# Interlock.net
KiCad netlist of a schematic drawn in Altium Designer
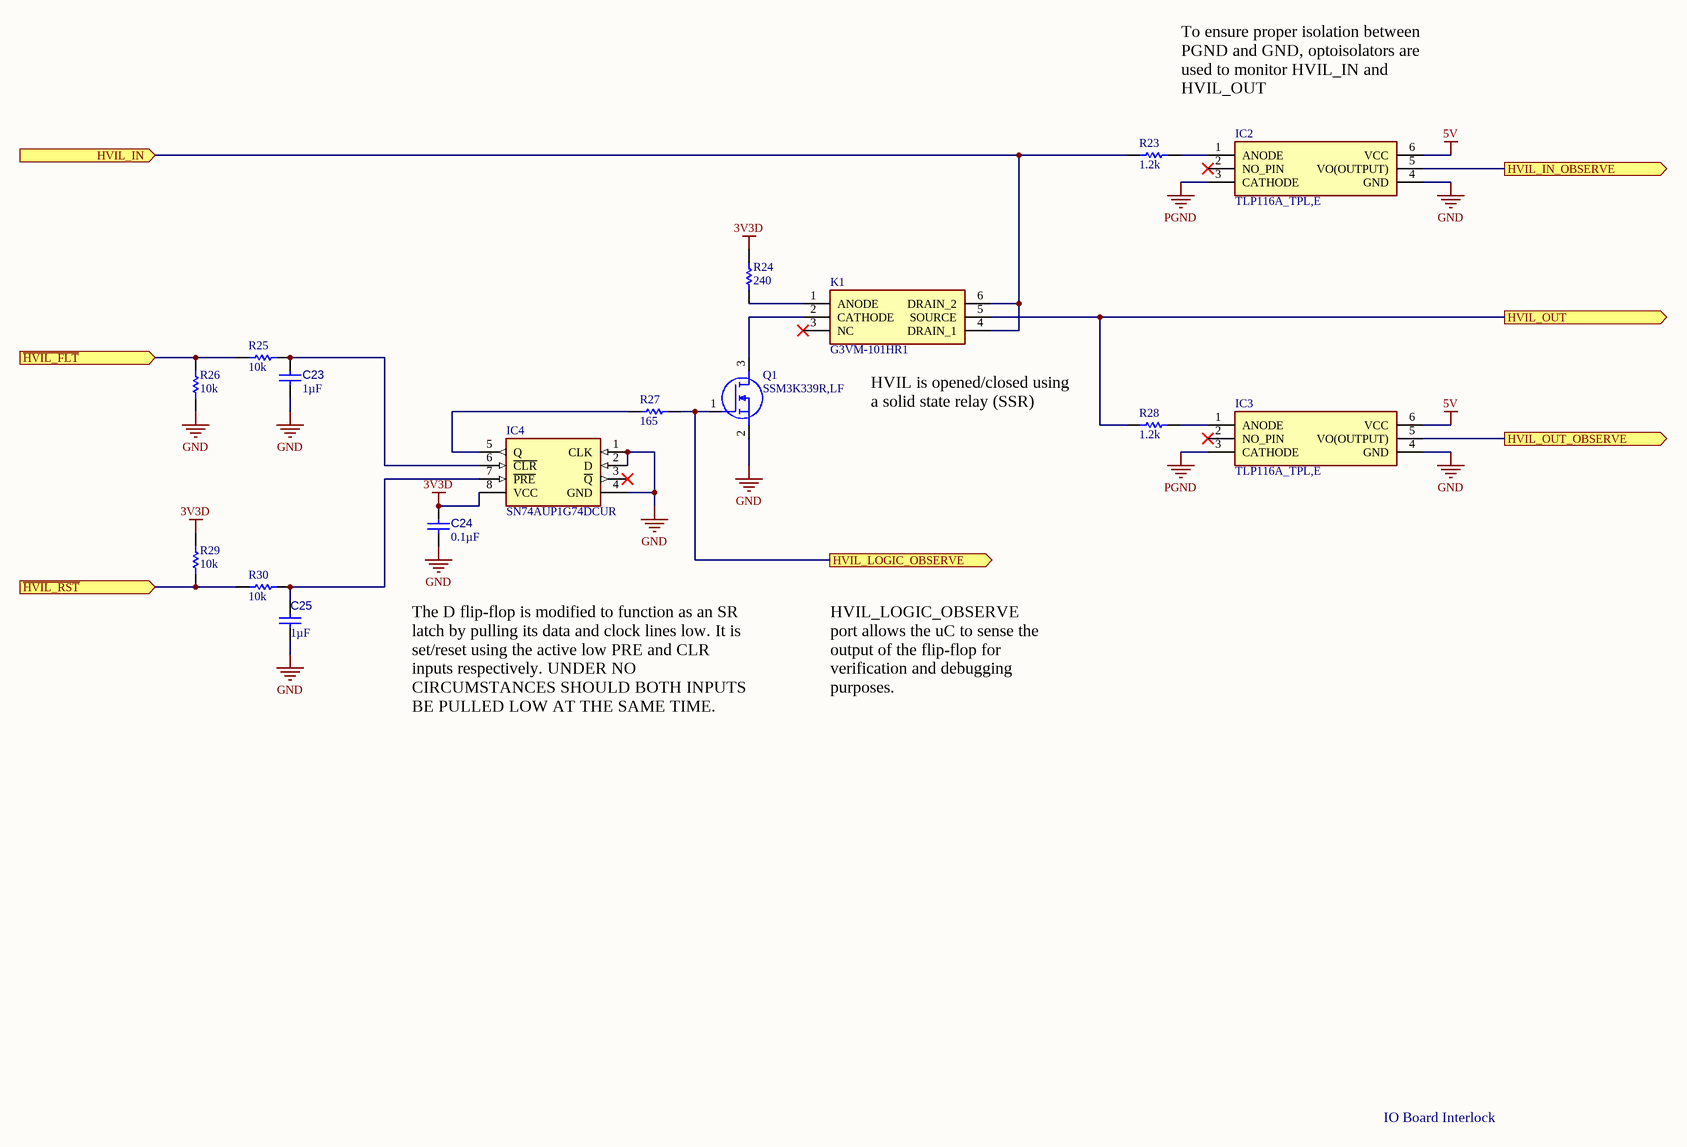
[diagram p0: Interlock.SchDoc]

(export (version "E")
  (design (tool "Eeschema 10.0.6"))
  (components
    (comp (ref "C23")
      (value "1µF")
      (footprint "CAPC2013X145X50ML20T25")
      (description "Chip Capacitor, 1 uF, +/-10%, 25 V, 0805 (2012 Metric)")
      (fields (field (name "TOLERANCE") "10%"))
      (libsource (lib "Caltech FSAE") (part "CAP-NP-2"))
    )
    (comp (ref "C24")
      (value "0.1µF")
      (footprint "CAPC2013X145X50ML20T25")
      (description "Chip Capacitor, 0.1 uF, +/-10%, 25 V, 0805 (2012 Metric)")
      (fields (field (name "TOLERANCE") "10%"))
      (libsource (lib "Caltech FSAE") (part "CAP-NP-2"))
    )
    (comp (ref "C25")
      (value "1µF")
      (footprint "CAPC2013X145X50ML20T25")
      (description "Chip Capacitor, 1 uF, +/-10%, 25 V, 0805 (2012 Metric)")
      (fields (field (name "TOLERANCE") "10%"))
      (libsource (lib "Caltech FSAE") (part "CAP-NP-2"))
    )
    (comp (ref "IC2")
      (value "TLP116A_TPL,E")
      (footprint "SOT127P700X230-6N")
      (description "Integrated Circuit")
      (fields
        (field (name "MANUFACTURER_PART_NUMBER") "TLP116A(TPL,E")
        (field (name "MOUSER PART NUMBER") "757-TLP116A(TPLE")
      )
      (libsource (lib "uControllerTemplate2021") (part "TLP116A_TPL,E"))
    )
    (comp (ref "IC3")
      (value "TLP116A_TPL,E")
      (footprint "SOT127P700X230-6N")
      (description "Integrated Circuit")
      (fields
        (field (name "MANUFACTURER_PART_NUMBER") "TLP116A(TPL,E")
        (field (name "MOUSER PART NUMBER") "757-TLP116A(TPLE")
      )
      (libsource (lib "uControllerTemplate2021") (part "TLP116A_TPL,E"))
    )
    (comp (ref "IC4")
      (value "SN74AUP1G74DCUR")
      (footprint "SOT50P310X90-8N")
      (description "Integrated Circuit")
      (fields (field (name "MOUSER PART NUMBER") "595-SN74AUP1G74DCUR"))
      (libsource (lib "uControllerTemplate2021") (part "SN74AUP1G74DCUR"))
    )
    (comp (ref "K1")
      (value "G3VM-101HR1")
      (footprint "G3VM101HR1")
      (description "Relay or Contactor")
      (fields (field (name "MOUSER PART NUMBER") "653-G3VM-101HR1"))
      (libsource (lib "uControllerTemplate2021") (part "G3VM-101HR1"))
    )
    (comp (ref "Q1")
      (value "SSM3K339R,LF")
      (footprint "SOTFL95P240X88-3N")
      (description "MOSFET (N-Channel)")
      (fields (field (name "MOUSER PART NUMBER") "757-SSM3K339RLF"))
      (libsource (lib "uControllerTemplate2021") (part "SSM3K339R,LF"))
    )
    (comp (ref "R23")
      (value "1.2k")
      (footprint "RESC2013X50X35ML15T15")
      (description "Chip Resistor, 1.2k Ohm, +/- 1%, 125 mW, -55 to 155 degC, 0805 (2012 Metric)")
      (fields (field (name "TOLERANCE") "1%") (field (name "POWER") "125mW"))
      (libsource (lib "Caltech FSAE") (part "RES-2"))
    )
    (comp (ref "R24")
      (value "240")
      (footprint "RESC2013X50X35ML15T15")
      (description "Chip Resistor, 240 Ohm, +/- 1%, 125 mW, -55 to 155 degC, 0805 (2012 Metric)")
      (fields (field (name "TOLERANCE") "1%") (field (name "POWER") "125mW"))
      (libsource (lib "Caltech FSAE") (part "RES-2"))
    )
    (comp (ref "R25")
      (value "10k")
      (footprint "RESC2013X50X35ML15T15")
      (description "Chip Resistor, 10k Ohm, +/- 1%, 125 mW, -55 to 155 degC, 0805 (2012 Metric)")
      (fields (field (name "TOLERANCE") "1%") (field (name "POWER") "125mW"))
      (libsource (lib "Caltech FSAE") (part "RES-2"))
    )
    (comp (ref "R26")
      (value "10k")
      (footprint "RESC2013X50X35ML15T15")
      (description "Chip Resistor, 1.2k Ohm, +/- 1%, 125 mW, -55 to 155 degC, 0805 (2012 Metric)")
      (fields (field (name "TOLERANCE") "1%") (field (name "POWER") "125mW"))
      (libsource (lib "Caltech FSAE") (part "RES-2"))
    )
    (comp (ref "R27")
      (value "165")
      (footprint "RESC2013X50X35ML15T15")
      (description "Chip Resistor, 165 Ohm, +/- 1%, 125 mW, -55 to 155 degC, 0805 (2012 Metric)")
      (fields (field (name "TOLERANCE") "1%") (field (name "POWER") "125mW"))
      (libsource (lib "Caltech FSAE") (part "RES-2"))
    )
    (comp (ref "R28")
      (value "1.2k")
      (footprint "RESC2013X50X35ML15T15")
      (description "Chip Resistor, 1.2k Ohm, +/- 1%, 125 mW, -55 to 155 degC, 0805 (2012 Metric)")
      (fields (field (name "TOLERANCE") "1%") (field (name "POWER") "125mW"))
      (libsource (lib "Caltech FSAE") (part "RES-2"))
    )
    (comp (ref "R29")
      (value "10k")
      (footprint "RESC2013X50X35ML15T15")
      (description "Chip Resistor, 10k Ohm, +/- 1%, 125 mW, -55 to 155 degC, 0805 (2012 Metric)")
      (fields (field (name "TOLERANCE") "1%") (field (name "POWER") "125mW"))
      (libsource (lib "Caltech FSAE") (part "RES-2"))
    )
    (comp (ref "R30")
      (value "10k")
      (footprint "RESC2013X50X35ML15T15")
      (description "Chip Resistor, 10k Ohm, +/- 1%, 125 mW, -55 to 155 degC, 0805 (2012 Metric)")
      (fields (field (name "TOLERANCE") "1%") (field (name "POWER") "125mW"))
      (libsource (lib "Caltech FSAE") (part "RES-2"))
    )
  )
  (nets
    (net (code "1") (name "/HVIL_IN") (class "Default")
      (node (ref "K1") (pin "4") (pinfunction "DRAIN_1_4") (pintype "passive"))
      (node (ref "K1") (pin "6") (pinfunction "DRAIN_2_6") (pintype "passive"))
      (node (ref "R23") (pin "1") (pinfunction "1_1") (pintype "passive"))
    )
    (net (code "2") (name "/HVIL_IN_OBSERVE") (class "Default")
      (node (ref "IC2") (pin "5") (pinfunction "VO(OUTPUT)_5") (pintype "passive"))
    )
    (net (code "3") (name "/HVIL_LOGIC_OBSERVE") (class "Default")
      (node (ref "Q1") (pin "1") (pinfunction "G_1") (pintype "passive"))
      (node (ref "R27") (pin "2") (pinfunction "2_2") (pintype "passive"))
    )
    (net (code "4") (name "/HVIL_OUT") (class "Default")
      (node (ref "K1") (pin "5") (pinfunction "SOURCE_5") (pintype "passive"))
      (node (ref "R28") (pin "1") (pinfunction "1_1") (pintype "passive"))
    )
    (net (code "5") (name "/HVIL_OUT_OBSERVE") (class "Default")
      (node (ref "IC3") (pin "5") (pinfunction "VO(OUTPUT)_5") (pintype "passive"))
    )
    (net (code "6") (name "/~{HVIL_FLT}") (class "Default")
      (node (ref "R25") (pin "2") (pinfunction "2_2") (pintype "passive"))
      (node (ref "R26") (pin "2") (pinfunction "2_2") (pintype "passive"))
    )
    (net (code "7") (name "/~{HVIL_RST}") (class "Default")
      (node (ref "R29") (pin "1") (pinfunction "1_1") (pintype "passive"))
      (node (ref "R30") (pin "2") (pinfunction "2_2") (pintype "passive"))
    )
    (net (code "8") (name "3V3D") (class "Default")
      (node (ref "C24") (pin "2") (pinfunction "2_2") (pintype "passive"))
      (node (ref "IC4") (pin "8") (pinfunction "VCC_8") (pintype "power_in"))
      (node (ref "R24") (pin "1") (pinfunction "1_1") (pintype "passive"))
      (node (ref "R29") (pin "2") (pinfunction "2_2") (pintype "passive"))
    )
    (net (code "9") (name "5V") (class "Default")
      (node (ref "IC2") (pin "6") (pinfunction "VCC_6") (pintype "passive"))
      (node (ref "IC3") (pin "6") (pinfunction "VCC_6") (pintype "passive"))
    )
    (net (code "10") (name "GND") (class "Default")
      (node (ref "C23") (pin "2") (pinfunction "2_2") (pintype "passive"))
      (node (ref "C24") (pin "1") (pinfunction "1_1") (pintype "passive"))
      (node (ref "C25") (pin "1") (pinfunction "1_1") (pintype "passive"))
      (node (ref "IC2") (pin "4") (pinfunction "GND_4") (pintype "passive"))
      (node (ref "IC3") (pin "4") (pinfunction "GND_4") (pintype "passive"))
      (node (ref "IC4") (pin "1") (pinfunction "CLK_1") (pintype "input"))
      (node (ref "IC4") (pin "2") (pinfunction "D_2") (pintype "input"))
      (node (ref "IC4") (pin "4") (pinfunction "GND_4") (pintype "power_in"))
      (node (ref "Q1") (pin "2") (pinfunction "S_2") (pintype "passive"))
      (node (ref "R26") (pin "1") (pinfunction "1_1") (pintype "passive"))
    )
    (net (code "11") (name "Net-(IC2-ANODE)") (class "Default")
      (node (ref "IC2") (pin "1") (pinfunction "ANODE_1") (pintype "passive"))
      (node (ref "R23") (pin "2") (pinfunction "2_2") (pintype "passive"))
    )
    (net (code "12") (name "Net-(IC3-ANODE)") (class "Default")
      (node (ref "IC3") (pin "1") (pinfunction "ANODE_1") (pintype "passive"))
      (node (ref "R28") (pin "2") (pinfunction "2_2") (pintype "passive"))
    )
    (net (code "13") (name "Net-(IC4-Q)") (class "Default")
      (node (ref "IC4") (pin "5") (pinfunction "Q_5") (pintype "output"))
      (node (ref "R27") (pin "1") (pinfunction "1_1") (pintype "passive"))
    )
    (net (code "14") (name "Net-(IC4-~{CLR})") (class "Default")
      (node (ref "C23") (pin "1") (pinfunction "1_1") (pintype "passive"))
      (node (ref "IC4") (pin "6") (pinfunction "~{CLR}_6") (pintype "input"))
      (node (ref "R25") (pin "1") (pinfunction "1_1") (pintype "passive"))
    )
    (net (code "15") (name "Net-(IC4-~{PRE})") (class "Default")
      (node (ref "C25") (pin "2") (pinfunction "2_2") (pintype "passive"))
      (node (ref "IC4") (pin "7") (pinfunction "~{PRE}_7") (pintype "input"))
      (node (ref "R30") (pin "1") (pinfunction "1_1") (pintype "passive"))
    )
    (net (code "16") (name "Net-(K1-ANODE)") (class "Default")
      (node (ref "K1") (pin "1") (pinfunction "ANODE_1") (pintype "passive"))
      (node (ref "R24") (pin "2") (pinfunction "2_2") (pintype "passive"))
    )
    (net (code "17") (name "Net-(K1-CATHODE)") (class "Default")
      (node (ref "K1") (pin "2") (pinfunction "CATHODE_2") (pintype "passive"))
      (node (ref "Q1") (pin "3") (pinfunction "D_3") (pintype "passive"))
    )
    (net (code "18") (name "PGND") (class "Default")
      (node (ref "IC2") (pin "3") (pinfunction "CATHODE_3") (pintype "passive"))
      (node (ref "IC3") (pin "3") (pinfunction "CATHODE_3") (pintype "passive"))
    )
    (net (code "19") (name "unconnected-(IC2-NO_PIN-Pad2)") (class "Default")
      (node (ref "IC2") (pin "2") (pinfunction "NO_PIN_2") (pintype "passive+no_connect"))
    )
    (net (code "20") (name "unconnected-(IC3-NO_PIN-Pad2)") (class "Default")
      (node (ref "IC3") (pin "2") (pinfunction "NO_PIN_2") (pintype "passive+no_connect"))
    )
    (net (code "21") (name "unconnected-(IC4-~{Q}-Pad3)") (class "Default")
      (node (ref "IC4") (pin "3") (pinfunction "~{Q}_3") (pintype "output+no_connect"))
    )
    (net (code "22") (name "unconnected-(K1-NC-Pad3)") (class "Default")
      (node (ref "K1") (pin "3") (pinfunction "NC_3") (pintype "passive+no_connect"))
    )
  )
)
